# KegWasher_1_2_Schematic_EasyEDA.net
KiCad netlist of a schematic drawn in EasyEDA
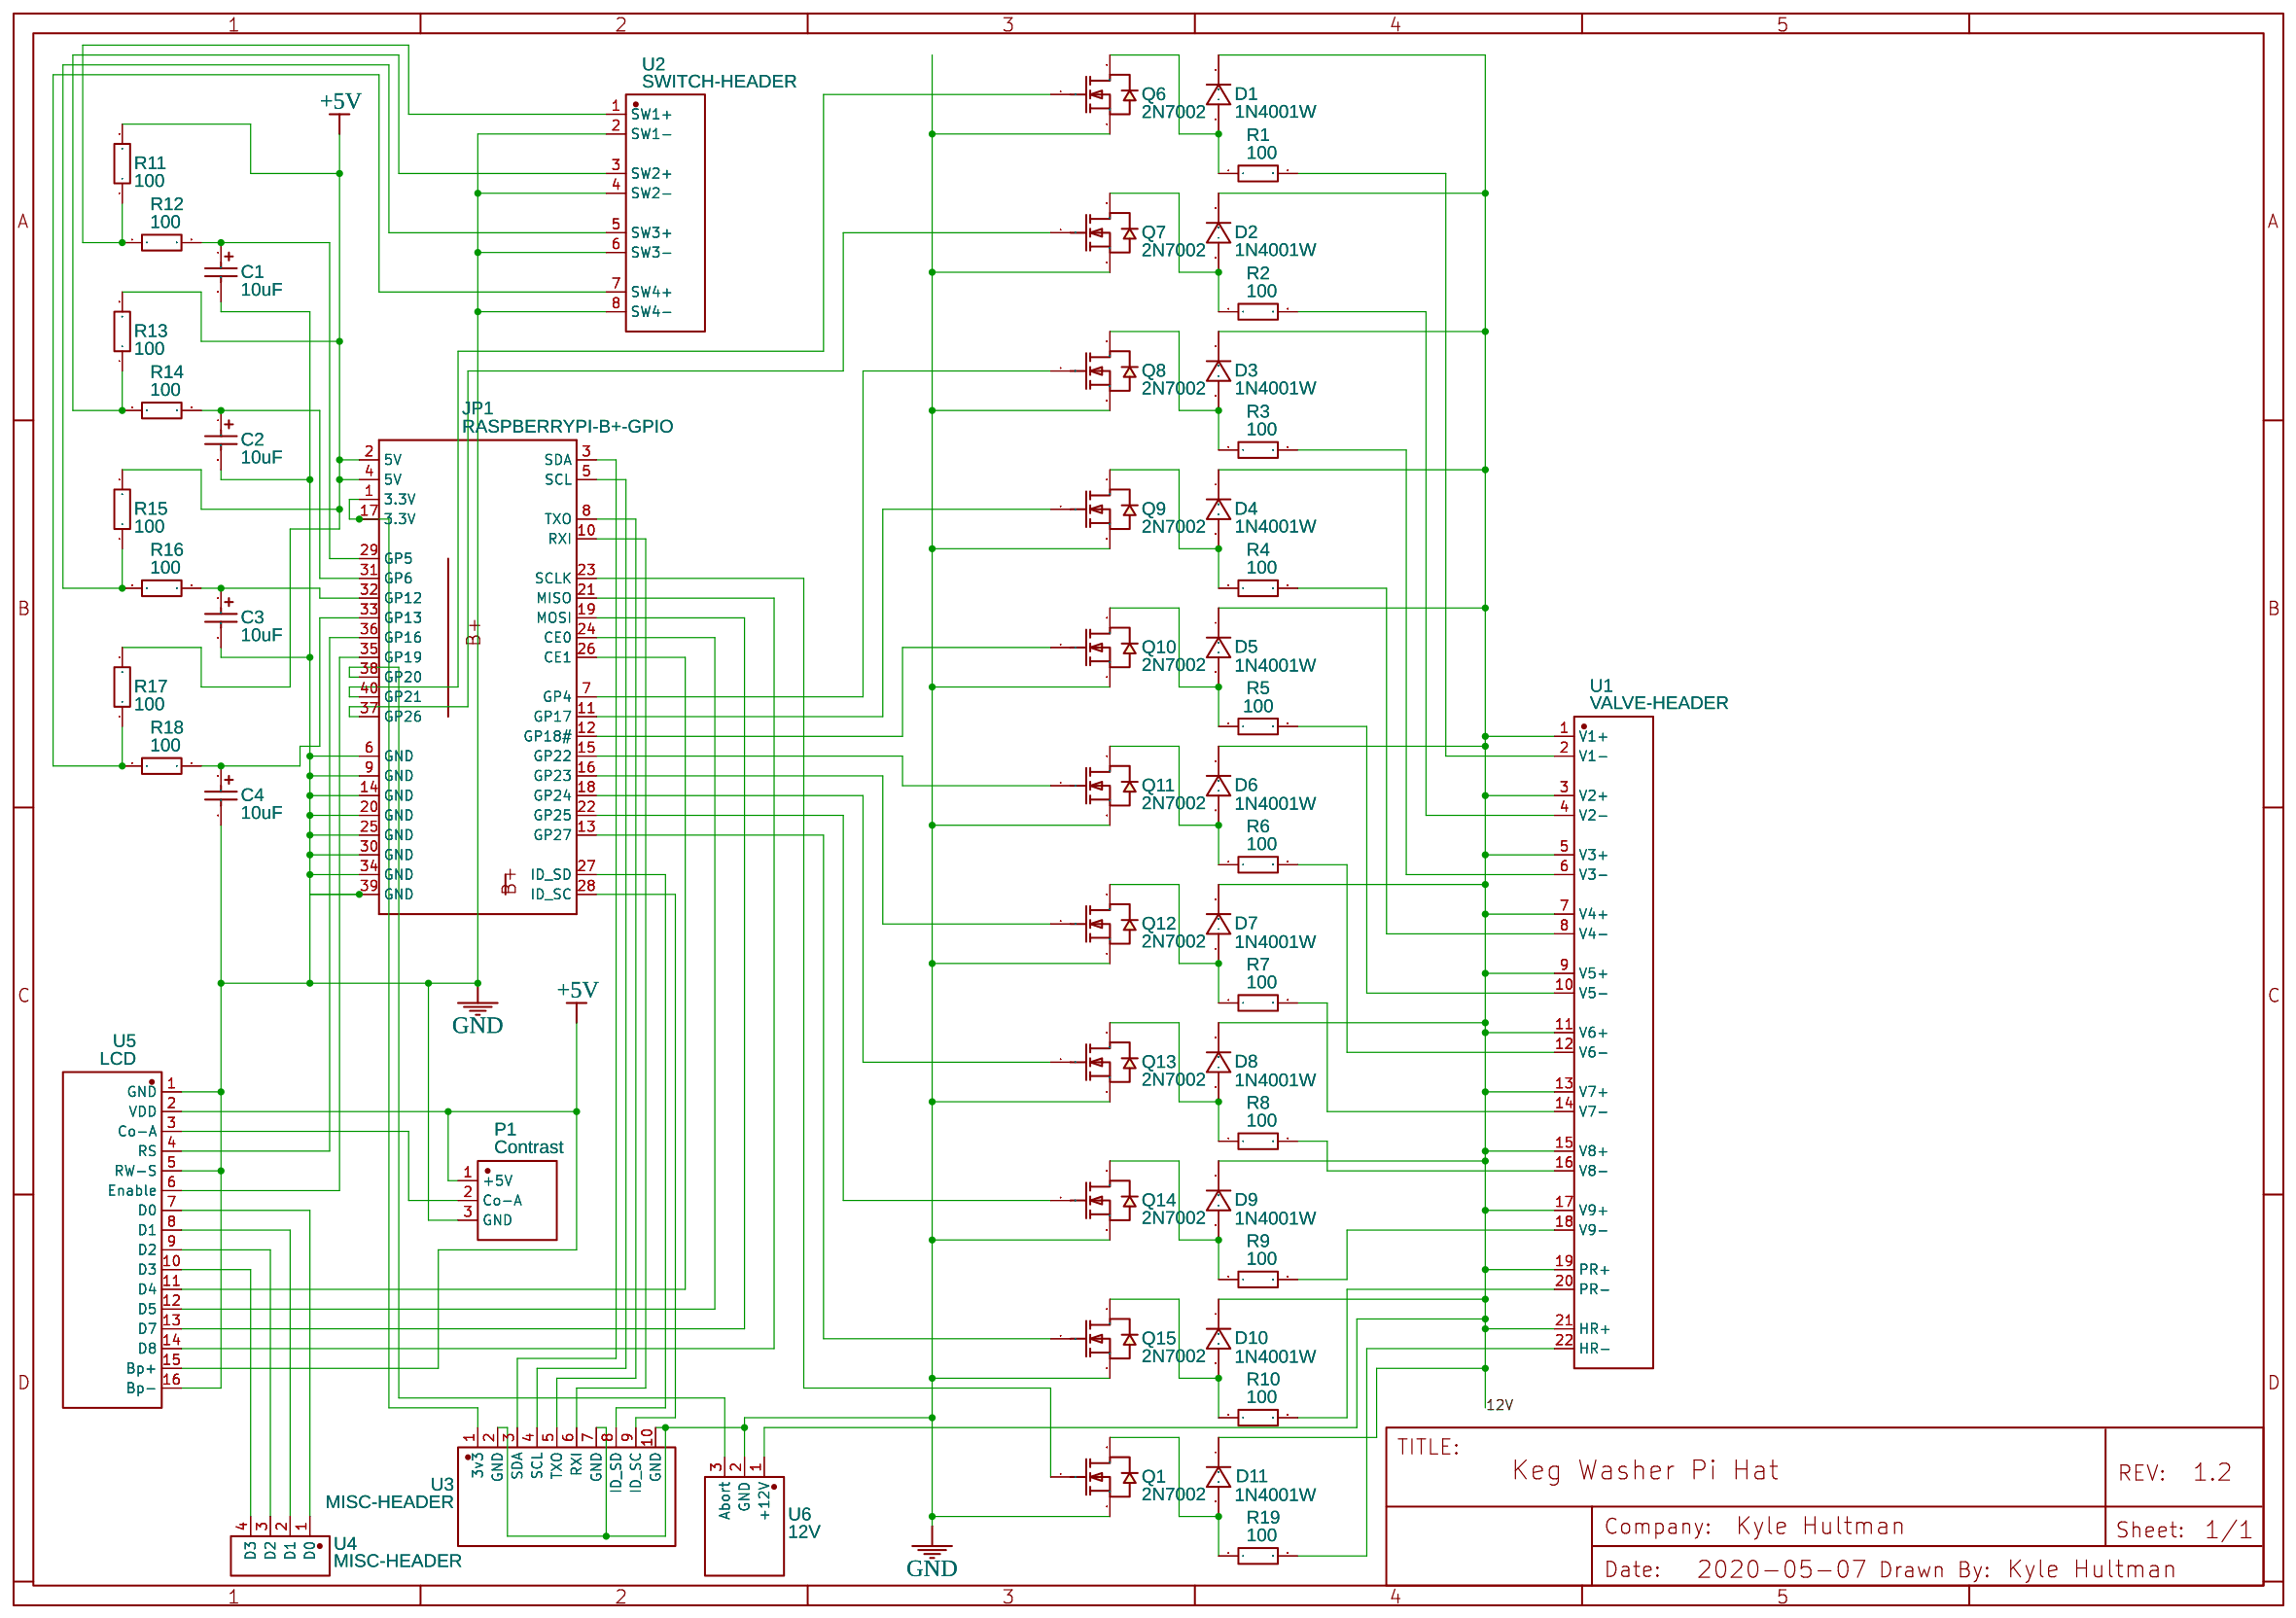
[diagram p0: schematic sheet]

(export (version "E")
  (design (tool "Eeschema 10.0.6"))
  (components
    (comp (ref "C1")
      (value "10uF")
      (fields
        (field (name "BOM_Manufacturer Part") "TAJA106K016RNJ")
        (field (name "BOM_Supplier Part") "C7171")
      )
      (libsource (lib "") (part "TAJA106K016RNJ"))
    )
    (comp (ref "C2")
      (value "10uF")
      (fields
        (field (name "BOM_Manufacturer Part") "TAJA106K016RNJ")
        (field (name "BOM_Supplier Part") "C7171")
      )
      (libsource (lib "") (part "TAJA106K016RNJ"))
    )
    (comp (ref "C3")
      (value "10uF")
      (fields
        (field (name "BOM_Manufacturer Part") "TAJA106K016RNJ")
        (field (name "BOM_Supplier Part") "C7171")
      )
      (libsource (lib "") (part "TAJA106K016RNJ"))
    )
    (comp (ref "C4")
      (value "10uF")
      (fields
        (field (name "BOM_Manufacturer Part") "TAJA106K016RNJ")
        (field (name "BOM_Supplier Part") "C7171")
      )
      (libsource (lib "") (part "TAJA106K016RNJ"))
    )
    (comp (ref "D1")
      (value "1N4001W")
      (fields (field (name "BOM_Supplier Part") "C162732"))
      (libsource (lib "") (part "1N4001W"))
    )
    (comp (ref "D2")
      (value "1N4001W")
      (fields (field (name "BOM_Supplier Part") "C162732"))
      (libsource (lib "") (part "1N4001W"))
    )
    (comp (ref "D3")
      (value "1N4001W")
      (fields (field (name "BOM_Supplier Part") "C162732"))
      (libsource (lib "") (part "1N4001W"))
    )
    (comp (ref "D4")
      (value "1N4001W")
      (fields (field (name "BOM_Supplier Part") "C162732"))
      (libsource (lib "") (part "1N4001W"))
    )
    (comp (ref "D5")
      (value "1N4001W")
      (fields (field (name "BOM_Supplier Part") "C162732"))
      (libsource (lib "") (part "1N4001W"))
    )
    (comp (ref "D6")
      (value "1N4001W")
      (fields (field (name "BOM_Supplier Part") "C162732"))
      (libsource (lib "") (part "1N4001W"))
    )
    (comp (ref "D7")
      (value "1N4001W")
      (fields (field (name "BOM_Supplier Part") "C162732"))
      (libsource (lib "") (part "1N4001W"))
    )
    (comp (ref "D8")
      (value "1N4001W")
      (fields (field (name "BOM_Supplier Part") "C162732"))
      (libsource (lib "") (part "1N4001W"))
    )
    (comp (ref "D9")
      (value "1N4001W")
      (fields (field (name "BOM_Supplier Part") "C162732"))
      (libsource (lib "") (part "1N4001W"))
    )
    (comp (ref "D10")
      (value "1N4001W")
      (fields (field (name "BOM_Supplier Part") "C162732"))
      (libsource (lib "") (part "1N4001W"))
    )
    (comp (ref "D11")
      (value "1N4001W")
      (fields (field (name "BOM_Supplier Part") "C162732"))
      (libsource (lib "") (part "1N4001W"))
    )
    (comp (ref "JP1") (value "RASPBERRYPI-B+-GPIO") (libsource (lib "") (part "RASPBERRYPI-B+-GPIO")))
    (comp (ref "P1") (value "Contrast") (libsource (lib "") (part "Contrast")))
    (comp (ref "Q1")
      (value "2N7002")
      (fields (field (name "BOM_Supplier Part") "C8545"))
      (libsource (lib "") (part "2N7002"))
    )
    (comp (ref "Q6")
      (value "2N7002")
      (fields (field (name "BOM_Supplier Part") "C8545"))
      (libsource (lib "") (part "2N7002"))
    )
    (comp (ref "Q7")
      (value "2N7002")
      (fields (field (name "BOM_Supplier Part") "C8545"))
      (libsource (lib "") (part "2N7002"))
    )
    (comp (ref "Q8")
      (value "2N7002")
      (fields (field (name "BOM_Supplier Part") "C8545"))
      (libsource (lib "") (part "2N7002"))
    )
    (comp (ref "Q9")
      (value "2N7002")
      (fields (field (name "BOM_Supplier Part") "C8545"))
      (libsource (lib "") (part "2N7002"))
    )
    (comp (ref "Q10")
      (value "2N7002")
      (fields (field (name "BOM_Supplier Part") "C8545"))
      (libsource (lib "") (part "2N7002"))
    )
    (comp (ref "Q11")
      (value "2N7002")
      (fields (field (name "BOM_Supplier Part") "C8545"))
      (libsource (lib "") (part "2N7002"))
    )
    (comp (ref "Q12")
      (value "2N7002")
      (fields (field (name "BOM_Supplier Part") "C8545"))
      (libsource (lib "") (part "2N7002"))
    )
    (comp (ref "Q13")
      (value "2N7002")
      (fields (field (name "BOM_Supplier Part") "C8545"))
      (libsource (lib "") (part "2N7002"))
    )
    (comp (ref "Q14")
      (value "2N7002")
      (fields (field (name "BOM_Supplier Part") "C8545"))
      (libsource (lib "") (part "2N7002"))
    )
    (comp (ref "Q15")
      (value "2N7002")
      (fields (field (name "BOM_Supplier Part") "C8545"))
      (libsource (lib "") (part "2N7002"))
    )
    (comp (ref "R1")
      (value "100")
      (fields
        (field (name "BOM_Manufacturer Part") "0805W8F1000T5E")
        (field (name "BOM_Supplier Part") "C17408")
      )
      (libsource (lib "") (part "0805W8F1000T5E"))
    )
    (comp (ref "R2")
      (value "100")
      (fields
        (field (name "BOM_Manufacturer Part") "0805W8F1000T5E")
        (field (name "BOM_Supplier Part") "C17408")
      )
      (libsource (lib "") (part "0805W8F1000T5E"))
    )
    (comp (ref "R3")
      (value "100")
      (fields
        (field (name "BOM_Manufacturer Part") "0805W8F1000T5E")
        (field (name "BOM_Supplier Part") "C17408")
      )
      (libsource (lib "") (part "0805W8F1000T5E"))
    )
    (comp (ref "R4")
      (value "100")
      (fields
        (field (name "BOM_Manufacturer Part") "0805W8F1000T5E")
        (field (name "BOM_Supplier Part") "C17408")
      )
      (libsource (lib "") (part "0805W8F1000T5E"))
    )
    (comp (ref "R5")
      (value "100")
      (fields
        (field (name "BOM_Manufacturer Part") "0805W8F1000T5E")
        (field (name "BOM_Supplier Part") "C17408")
      )
      (libsource (lib "") (part "0805W8F1000T5E"))
    )
    (comp (ref "R6")
      (value "100")
      (fields
        (field (name "BOM_Manufacturer Part") "0805W8F1000T5E")
        (field (name "BOM_Supplier Part") "C17408")
      )
      (libsource (lib "") (part "0805W8F1000T5E"))
    )
    (comp (ref "R7")
      (value "100")
      (fields
        (field (name "BOM_Manufacturer Part") "0805W8F1000T5E")
        (field (name "BOM_Supplier Part") "C17408")
      )
      (libsource (lib "") (part "0805W8F1000T5E"))
    )
    (comp (ref "R8")
      (value "100")
      (fields
        (field (name "BOM_Manufacturer Part") "0805W8F1000T5E")
        (field (name "BOM_Supplier Part") "C17408")
      )
      (libsource (lib "") (part "0805W8F1000T5E"))
    )
    (comp (ref "R9")
      (value "100")
      (fields
        (field (name "BOM_Manufacturer Part") "0805W8F1000T5E")
        (field (name "BOM_Supplier Part") "C17408")
      )
      (libsource (lib "") (part "0805W8F1000T5E"))
    )
    (comp (ref "R10")
      (value "100")
      (fields
        (field (name "BOM_Manufacturer Part") "0805W8F1000T5E")
        (field (name "BOM_Supplier Part") "C17408")
      )
      (libsource (lib "") (part "0805W8F1000T5E"))
    )
    (comp (ref "R11")
      (value "100")
      (fields
        (field (name "BOM_Manufacturer Part") "0805W8F1000T5E")
        (field (name "BOM_Supplier Part") "C17408")
      )
      (libsource (lib "") (part "0805W8F1000T5E_1"))
    )
    (comp (ref "R12")
      (value "100")
      (fields
        (field (name "BOM_Manufacturer Part") "0805W8F1000T5E")
        (field (name "BOM_Supplier Part") "C17408")
      )
      (libsource (lib "") (part "0805W8F1000T5E"))
    )
    (comp (ref "R13")
      (value "100")
      (fields
        (field (name "BOM_Manufacturer Part") "0805W8F1000T5E")
        (field (name "BOM_Supplier Part") "C17408")
      )
      (libsource (lib "") (part "0805W8F1000T5E_1"))
    )
    (comp (ref "R14")
      (value "100")
      (fields
        (field (name "BOM_Manufacturer Part") "0805W8F1000T5E")
        (field (name "BOM_Supplier Part") "C17408")
      )
      (libsource (lib "") (part "0805W8F1000T5E"))
    )
    (comp (ref "R15")
      (value "100")
      (fields
        (field (name "BOM_Manufacturer Part") "0805W8F1000T5E")
        (field (name "BOM_Supplier Part") "C17408")
      )
      (libsource (lib "") (part "0805W8F1000T5E_1"))
    )
    (comp (ref "R16")
      (value "100")
      (fields
        (field (name "BOM_Manufacturer Part") "0805W8F1000T5E")
        (field (name "BOM_Supplier Part") "C17408")
      )
      (libsource (lib "") (part "0805W8F1000T5E"))
    )
    (comp (ref "R17")
      (value "100")
      (fields
        (field (name "BOM_Manufacturer Part") "0805W8F1000T5E")
        (field (name "BOM_Supplier Part") "C17408")
      )
      (libsource (lib "") (part "0805W8F1000T5E_1"))
    )
    (comp (ref "R18")
      (value "100")
      (fields
        (field (name "BOM_Manufacturer Part") "0805W8F1000T5E")
        (field (name "BOM_Supplier Part") "C17408")
      )
      (libsource (lib "") (part "0805W8F1000T5E"))
    )
    (comp (ref "R19")
      (value "100")
      (fields
        (field (name "BOM_Manufacturer Part") "0805W8F1000T5E")
        (field (name "BOM_Supplier Part") "C17408")
      )
      (libsource (lib "") (part "0805W8F1000T5E"))
    )
    (comp (ref "U1") (value "VALVE-HEADER") (libsource (lib "") (part "VALVE-HEADER")))
    (comp (ref "U2") (value "SWITCH-HEADER") (libsource (lib "") (part "SWITCH-HEADER")))
    (comp (ref "U3") (value "MISC-HEADER") (libsource (lib "") (part "MISC-HEADER_1")))
    (comp (ref "U4") (value "MISC-HEADER") (libsource (lib "") (part "MISC-HEADER")))
    (comp (ref "U5") (value "LCD") (libsource (lib "") (part "LCD")))
    (comp (ref "U6") (value "12V") (libsource (lib "") (part "12V")))
  )
  (nets
    (net (code "1") (name "+5V") (class "Default")
      (node (ref "JP1") (pin "2") (pinfunction "5V_2") (pintype "passive"))
      (node (ref "JP1") (pin "4") (pinfunction "5V_4") (pintype "passive"))
      (node (ref "P1") (pin "1") (pinfunction "+5V_1") (pintype "unspecified"))
      (node (ref "R11") (pin "2") (pinfunction "2_2") (pintype "input"))
      (node (ref "R13") (pin "2") (pinfunction "2_2") (pintype "input"))
      (node (ref "R15") (pin "2") (pinfunction "2_2") (pintype "input"))
      (node (ref "R17") (pin "2") (pinfunction "2_2") (pintype "input"))
      (node (ref "U5") (pin "15") (pinfunction "Bp+_15") (pintype "unspecified"))
      (node (ref "U5") (pin "2") (pinfunction "VDD_2") (pintype "unspecified"))
    )
    (net (code "2") (name "/12V") (class "Default")
      (node (ref "D1") (pin "1") (pinfunction "C_1") (pintype "unspecified"))
      (node (ref "D10") (pin "1") (pinfunction "C_1") (pintype "unspecified"))
      (node (ref "D11") (pin "1") (pinfunction "C_1") (pintype "unspecified"))
      (node (ref "D2") (pin "1") (pinfunction "C_1") (pintype "unspecified"))
      (node (ref "D3") (pin "1") (pinfunction "C_1") (pintype "unspecified"))
      (node (ref "D4") (pin "1") (pinfunction "C_1") (pintype "unspecified"))
      (node (ref "D5") (pin "1") (pinfunction "C_1") (pintype "unspecified"))
      (node (ref "D6") (pin "1") (pinfunction "C_1") (pintype "unspecified"))
      (node (ref "D7") (pin "1") (pinfunction "C_1") (pintype "unspecified"))
      (node (ref "D8") (pin "1") (pinfunction "C_1") (pintype "unspecified"))
      (node (ref "D9") (pin "1") (pinfunction "C_1") (pintype "unspecified"))
      (node (ref "U1") (pin "1") (pinfunction "V1+_1") (pintype "unspecified"))
      (node (ref "U1") (pin "11") (pinfunction "V6+_11") (pintype "unspecified"))
      (node (ref "U1") (pin "13") (pinfunction "V7+_13") (pintype "unspecified"))
      (node (ref "U1") (pin "15") (pinfunction "V8+_15") (pintype "unspecified"))
      (node (ref "U1") (pin "17") (pinfunction "V9+_17") (pintype "unspecified"))
      (node (ref "U1") (pin "19") (pinfunction "PR+_19") (pintype "unspecified"))
      (node (ref "U1") (pin "21") (pinfunction "HR+_21") (pintype "unspecified"))
      (node (ref "U1") (pin "3") (pinfunction "V2+_3") (pintype "unspecified"))
      (node (ref "U1") (pin "5") (pinfunction "V3+_5") (pintype "unspecified"))
      (node (ref "U1") (pin "7") (pinfunction "V4+_7") (pintype "unspecified"))
      (node (ref "U1") (pin "9") (pinfunction "V5+_9") (pintype "unspecified"))
      (node (ref "U6") (pin "1") (pinfunction "+12V_1") (pintype "unspecified"))
    )
    (net (code "3") (name "GND") (class "Default")
      (node (ref "C1") (pin "2") (pinfunction "2_2") (pintype "input"))
      (node (ref "C2") (pin "2") (pinfunction "2_2") (pintype "input"))
      (node (ref "C3") (pin "2") (pinfunction "2_2") (pintype "input"))
      (node (ref "C4") (pin "2") (pinfunction "2_2") (pintype "input"))
      (node (ref "JP1") (pin "14") (pinfunction "GND_14") (pintype "passive"))
      (node (ref "JP1") (pin "20") (pinfunction "GND_20") (pintype "passive"))
      (node (ref "JP1") (pin "25") (pinfunction "GND_25") (pintype "passive"))
      (node (ref "JP1") (pin "30") (pinfunction "GND_30") (pintype "passive"))
      (node (ref "JP1") (pin "34") (pinfunction "GND_34") (pintype "passive"))
      (node (ref "JP1") (pin "39") (pinfunction "GND_39") (pintype "passive"))
      (node (ref "JP1") (pin "6") (pinfunction "GND_6") (pintype "passive"))
      (node (ref "JP1") (pin "9") (pinfunction "GND_9") (pintype "passive"))
      (node (ref "P1") (pin "3") (pinfunction "GND_3") (pintype "unspecified"))
      (node (ref "Q1") (pin "2") (pinfunction "S_2") (pintype "unspecified"))
      (node (ref "Q10") (pin "2") (pinfunction "S_2") (pintype "unspecified"))
      (node (ref "Q11") (pin "2") (pinfunction "S_2") (pintype "unspecified"))
      (node (ref "Q12") (pin "2") (pinfunction "S_2") (pintype "unspecified"))
      (node (ref "Q13") (pin "2") (pinfunction "S_2") (pintype "unspecified"))
      (node (ref "Q14") (pin "2") (pinfunction "S_2") (pintype "unspecified"))
      (node (ref "Q15") (pin "2") (pinfunction "S_2") (pintype "unspecified"))
      (node (ref "Q6") (pin "2") (pinfunction "S_2") (pintype "unspecified"))
      (node (ref "Q7") (pin "2") (pinfunction "S_2") (pintype "unspecified"))
      (node (ref "Q8") (pin "2") (pinfunction "S_2") (pintype "unspecified"))
      (node (ref "Q9") (pin "2") (pinfunction "S_2") (pintype "unspecified"))
      (node (ref "U2") (pin "2") (pinfunction "SW1-_2") (pintype "unspecified"))
      (node (ref "U2") (pin "4") (pinfunction "SW2-_4") (pintype "unspecified"))
      (node (ref "U2") (pin "6") (pinfunction "SW3-_6") (pintype "unspecified"))
      (node (ref "U2") (pin "8") (pinfunction "SW4-_8") (pintype "unspecified"))
      (node (ref "U3") (pin "10") (pinfunction "GND_10") (pintype "unspecified"))
      (node (ref "U3") (pin "2") (pinfunction "GND_2") (pintype "unspecified"))
      (node (ref "U3") (pin "7") (pinfunction "GND_7") (pintype "unspecified"))
      (node (ref "U5") (pin "1") (pinfunction "GND_1") (pintype "unspecified"))
      (node (ref "U5") (pin "16") (pinfunction "Bp-_16") (pintype "unspecified"))
      (node (ref "U5") (pin "5") (pinfunction "RW-S_5") (pintype "unspecified"))
      (node (ref "U6") (pin "2") (pinfunction "GND_2") (pintype "unspecified"))
    )
    (net (code "4") (name "Net-(D1-A)") (class "Default")
      (node (ref "D1") (pin "2") (pinfunction "A_2") (pintype "unspecified"))
      (node (ref "Q6") (pin "3") (pinfunction "D_3") (pintype "unspecified"))
      (node (ref "R1") (pin "1") (pinfunction "1_1") (pintype "input"))
    )
    (net (code "5") (name "Net-(D2-A)") (class "Default")
      (node (ref "D2") (pin "2") (pinfunction "A_2") (pintype "unspecified"))
      (node (ref "Q7") (pin "3") (pinfunction "D_3") (pintype "unspecified"))
      (node (ref "R2") (pin "1") (pinfunction "1_1") (pintype "input"))
    )
    (net (code "6") (name "Net-(D3-A)") (class "Default")
      (node (ref "D3") (pin "2") (pinfunction "A_2") (pintype "unspecified"))
      (node (ref "Q8") (pin "3") (pinfunction "D_3") (pintype "unspecified"))
      (node (ref "R3") (pin "1") (pinfunction "1_1") (pintype "input"))
    )
    (net (code "7") (name "Net-(D4-A)") (class "Default")
      (node (ref "D4") (pin "2") (pinfunction "A_2") (pintype "unspecified"))
      (node (ref "Q9") (pin "3") (pinfunction "D_3") (pintype "unspecified"))
      (node (ref "R4") (pin "1") (pinfunction "1_1") (pintype "input"))
    )
    (net (code "8") (name "Net-(D5-A)") (class "Default")
      (node (ref "D5") (pin "2") (pinfunction "A_2") (pintype "unspecified"))
      (node (ref "Q10") (pin "3") (pinfunction "D_3") (pintype "unspecified"))
      (node (ref "R5") (pin "1") (pinfunction "1_1") (pintype "input"))
    )
    (net (code "9") (name "Net-(D6-A)") (class "Default")
      (node (ref "D6") (pin "2") (pinfunction "A_2") (pintype "unspecified"))
      (node (ref "Q11") (pin "3") (pinfunction "D_3") (pintype "unspecified"))
      (node (ref "R6") (pin "1") (pinfunction "1_1") (pintype "input"))
    )
    (net (code "10") (name "Net-(D7-A)") (class "Default")
      (node (ref "D7") (pin "2") (pinfunction "A_2") (pintype "unspecified"))
      (node (ref "Q12") (pin "3") (pinfunction "D_3") (pintype "unspecified"))
      (node (ref "R7") (pin "1") (pinfunction "1_1") (pintype "input"))
    )
    (net (code "11") (name "Net-(D8-A)") (class "Default")
      (node (ref "D8") (pin "2") (pinfunction "A_2") (pintype "unspecified"))
      (node (ref "Q13") (pin "3") (pinfunction "D_3") (pintype "unspecified"))
      (node (ref "R8") (pin "1") (pinfunction "1_1") (pintype "input"))
    )
    (net (code "12") (name "Net-(D9-A)") (class "Default")
      (node (ref "D9") (pin "2") (pinfunction "A_2") (pintype "unspecified"))
      (node (ref "Q14") (pin "3") (pinfunction "D_3") (pintype "unspecified"))
      (node (ref "R9") (pin "1") (pinfunction "1_1") (pintype "input"))
    )
    (net (code "13") (name "Net-(D10-A)") (class "Default")
      (node (ref "D10") (pin "2") (pinfunction "A_2") (pintype "unspecified"))
      (node (ref "Q15") (pin "3") (pinfunction "D_3") (pintype "unspecified"))
      (node (ref "R10") (pin "1") (pinfunction "1_1") (pintype "input"))
    )
    (net (code "14") (name "Net-(D11-A)") (class "Default")
      (node (ref "D11") (pin "2") (pinfunction "A_2") (pintype "unspecified"))
      (node (ref "Q1") (pin "3") (pinfunction "D_3") (pintype "unspecified"))
      (node (ref "R19") (pin "1") (pinfunction "1_1") (pintype "input"))
    )
    (net (code "15") (name "Net-(JP1-CE0)") (class "Default")
      (node (ref "JP1") (pin "24") (pinfunction "CE0_24") (pintype "output"))
      (node (ref "U5") (pin "12") (pinfunction "D5_12") (pintype "unspecified"))
    )
    (net (code "16") (name "Net-(JP1-CE1)") (class "Default")
      (node (ref "JP1") (pin "26") (pinfunction "CE1_26") (pintype "output"))
      (node (ref "U5") (pin "11") (pinfunction "D4_11") (pintype "unspecified"))
    )
    (net (code "17") (name "Net-(JP1-GP4)") (class "Default")
      (node (ref "JP1") (pin "7") (pinfunction "GP4_7") (pintype "unspecified"))
      (node (ref "Q8") (pin "1") (pinfunction "G_1") (pintype "unspecified"))
    )
    (net (code "18") (name "Net-(JP1-GP5)") (class "Default")
      (node (ref "C1") (pin "1") (pinfunction "1_1") (pintype "input"))
      (node (ref "JP1") (pin "29") (pinfunction "GP5_29") (pintype "unspecified"))
      (node (ref "R12") (pin "2") (pinfunction "2_2") (pintype "input"))
    )
    (net (code "19") (name "Net-(JP1-GP6)") (class "Default")
      (node (ref "C2") (pin "1") (pinfunction "1_1") (pintype "input"))
      (node (ref "JP1") (pin "31") (pinfunction "GP6_31") (pintype "unspecified"))
      (node (ref "R14") (pin "2") (pinfunction "2_2") (pintype "input"))
    )
    (net (code "20") (name "Net-(JP1-GP12)") (class "Default")
      (node (ref "C3") (pin "1") (pinfunction "1_1") (pintype "input"))
      (node (ref "JP1") (pin "32") (pinfunction "GP12_32") (pintype "unspecified"))
      (node (ref "R16") (pin "2") (pinfunction "2_2") (pintype "input"))
    )
    (net (code "21") (name "Net-(JP1-GP13)") (class "Default")
      (node (ref "C4") (pin "1") (pinfunction "1_1") (pintype "input"))
      (node (ref "JP1") (pin "33") (pinfunction "GP13_33") (pintype "unspecified"))
      (node (ref "R18") (pin "2") (pinfunction "2_2") (pintype "input"))
    )
    (net (code "22") (name "Net-(JP1-GP16)") (class "Default")
      (node (ref "JP1") (pin "36") (pinfunction "GP16_36") (pintype "unspecified"))
      (node (ref "U5") (pin "4") (pinfunction "RS_4") (pintype "unspecified"))
    )
    (net (code "23") (name "Net-(JP1-GP17)") (class "Default")
      (node (ref "JP1") (pin "11") (pinfunction "GP17_11") (pintype "unspecified"))
      (node (ref "Q9") (pin "1") (pinfunction "G_1") (pintype "unspecified"))
    )
    (net (code "24") (name "Net-(JP1-GP18#)") (class "Default")
      (node (ref "JP1") (pin "12") (pinfunction "GP18#_12") (pintype "unspecified"))
      (node (ref "Q10") (pin "1") (pinfunction "G_1") (pintype "unspecified"))
    )
    (net (code "25") (name "Net-(JP1-GP19)") (class "Default")
      (node (ref "JP1") (pin "35") (pinfunction "GP19_35") (pintype "unspecified"))
      (node (ref "U5") (pin "6") (pinfunction "Enable_6") (pintype "unspecified"))
    )
    (net (code "26") (name "Net-(JP1-GP20)") (class "Default")
      (node (ref "JP1") (pin "38") (pinfunction "GP20_38") (pintype "unspecified"))
      (node (ref "U6") (pin "3") (pinfunction "Abort_3") (pintype "unspecified"))
    )
    (net (code "27") (name "Net-(JP1-GP21)") (class "Default")
      (node (ref "JP1") (pin "40") (pinfunction "GP21_40") (pintype "unspecified"))
      (node (ref "Q6") (pin "1") (pinfunction "G_1") (pintype "unspecified"))
    )
    (net (code "28") (name "Net-(JP1-GP22)") (class "Default")
      (node (ref "JP1") (pin "15") (pinfunction "GP22_15") (pintype "unspecified"))
      (node (ref "Q11") (pin "1") (pinfunction "G_1") (pintype "unspecified"))
    )
    (net (code "29") (name "Net-(JP1-GP23)") (class "Default")
      (node (ref "JP1") (pin "16") (pinfunction "GP23_16") (pintype "unspecified"))
      (node (ref "Q12") (pin "1") (pinfunction "G_1") (pintype "unspecified"))
    )
    (net (code "30") (name "Net-(JP1-GP24)") (class "Default")
      (node (ref "JP1") (pin "18") (pinfunction "GP24_18") (pintype "unspecified"))
      (node (ref "Q13") (pin "1") (pinfunction "G_1") (pintype "unspecified"))
    )
    (net (code "31") (name "Net-(JP1-GP25)") (class "Default")
      (node (ref "JP1") (pin "22") (pinfunction "GP25_22") (pintype "unspecified"))
      (node (ref "Q14") (pin "1") (pinfunction "G_1") (pintype "unspecified"))
    )
    (net (code "32") (name "Net-(JP1-GP26)") (class "Default")
      (node (ref "JP1") (pin "37") (pinfunction "GP26_37") (pintype "unspecified"))
      (node (ref "Q7") (pin "1") (pinfunction "G_1") (pintype "unspecified"))
    )
    (net (code "33") (name "Net-(JP1-GP27)") (class "Default")
      (node (ref "JP1") (pin "13") (pinfunction "GP27_13") (pintype "unspecified"))
      (node (ref "Q15") (pin "1") (pinfunction "G_1") (pintype "unspecified"))
    )
    (net (code "34") (name "Net-(JP1-ID_SC)") (class "Default")
      (node (ref "JP1") (pin "28") (pinfunction "ID_SC_28") (pintype "unspecified"))
      (node (ref "U3") (pin "9") (pinfunction "ID_SC_9") (pintype "unspecified"))
    )
    (net (code "35") (name "Net-(JP1-ID_SD)") (class "Default")
      (node (ref "JP1") (pin "27") (pinfunction "ID_SD_27") (pintype "unspecified"))
      (node (ref "U3") (pin "8") (pinfunction "ID_SD_8") (pintype "unspecified"))
    )
    (net (code "36") (name "Net-(JP1-MISO)") (class "Default")
      (node (ref "JP1") (pin "21") (pinfunction "MISO_21") (pintype "input"))
      (node (ref "U5") (pin "14") (pinfunction "D8_14") (pintype "unspecified"))
    )
    (net (code "37") (name "Net-(JP1-MOSI)") (class "Default")
      (node (ref "JP1") (pin "19") (pinfunction "MOSI_19") (pintype "output"))
      (node (ref "U5") (pin "13") (pinfunction "D7_13") (pintype "unspecified"))
    )
    (net (code "38") (name "Net-(JP1-RXI)") (class "Default")
      (node (ref "JP1") (pin "10") (pinfunction "RXI_10") (pintype "input"))
      (node (ref "U3") (pin "6") (pinfunction "RXI_6") (pintype "unspecified"))
    )
    (net (code "39") (name "Net-(JP1-SCL)") (class "Default")
      (node (ref "JP1") (pin "5") (pinfunction "SCL_5") (pintype "unspecified"))
      (node (ref "U3") (pin "4") (pinfunction "SCL_4") (pintype "unspecified"))
    )
    (net (code "40") (name "Net-(JP1-SCLK)") (class "Default")
      (node (ref "JP1") (pin "23") (pinfunction "SCLK_23") (pintype "output"))
      (node (ref "Q1") (pin "1") (pinfunction "G_1") (pintype "unspecified"))
    )
    (net (code "41") (name "Net-(JP1-SDA)") (class "Default")
      (node (ref "JP1") (pin "3") (pinfunction "SDA_3") (pintype "unspecified"))
      (node (ref "U3") (pin "3") (pinfunction "SDA_3") (pintype "unspecified"))
    )
    (net (code "42") (name "Net-(JP1-TXO)") (class "Default")
      (node (ref "JP1") (pin "8") (pinfunction "TXO_8") (pintype "output"))
      (node (ref "U3") (pin "5") (pinfunction "TXO_5") (pintype "unspecified"))
    )
    (net (code "43") (name "Net-(P1-Co-A)") (class "Default")
      (node (ref "P1") (pin "2") (pinfunction "Co-A_2") (pintype "unspecified"))
      (node (ref "U5") (pin "3") (pinfunction "Co-A_3") (pintype "unspecified"))
    )
    (net (code "44") (name "Net-(U1-HR-)") (class "Default")
      (node (ref "R19") (pin "2") (pinfunction "2_2") (pintype "input"))
      (node (ref "U1") (pin "22") (pinfunction "HR-_22") (pintype "unspecified"))
    )
    (net (code "45") (name "Net-(U1-PR-)") (class "Default")
      (node (ref "R10") (pin "2") (pinfunction "2_2") (pintype "input"))
      (node (ref "U1") (pin "20") (pinfunction "PR-_20") (pintype "unspecified"))
    )
    (net (code "46") (name "Net-(U1-V1-)") (class "Default")
      (node (ref "R1") (pin "2") (pinfunction "2_2") (pintype "input"))
      (node (ref "U1") (pin "2") (pinfunction "V1-_2") (pintype "unspecified"))
    )
    (net (code "47") (name "Net-(U1-V2-)") (class "Default")
      (node (ref "R2") (pin "2") (pinfunction "2_2") (pintype "input"))
      (node (ref "U1") (pin "4") (pinfunction "V2-_4") (pintype "unspecified"))
    )
    (net (code "48") (name "Net-(U1-V3-)") (class "Default")
      (node (ref "R3") (pin "2") (pinfunction "2_2") (pintype "input"))
      (node (ref "U1") (pin "6") (pinfunction "V3-_6") (pintype "unspecified"))
    )
    (net (code "49") (name "Net-(U1-V4-)") (class "Default")
      (node (ref "R4") (pin "2") (pinfunction "2_2") (pintype "input"))
      (node (ref "U1") (pin "8") (pinfunction "V4-_8") (pintype "unspecified"))
    )
    (net (code "50") (name "Net-(U1-V5-)") (class "Default")
      (node (ref "R5") (pin "2") (pinfunction "2_2") (pintype "input"))
      (node (ref "U1") (pin "10") (pinfunction "V5-_10") (pintype "unspecified"))
    )
    (net (code "51") (name "Net-(U1-V6-)") (class "Default")
      (node (ref "R6") (pin "2") (pinfunction "2_2") (pintype "input"))
      (node (ref "U1") (pin "12") (pinfunction "V6-_12") (pintype "unspecified"))
    )
    (net (code "52") (name "Net-(U1-V7-)") (class "Default")
      (node (ref "R7") (pin "2") (pinfunction "2_2") (pintype "input"))
      (node (ref "U1") (pin "14") (pinfunction "V7-_14") (pintype "unspecified"))
    )
    (net (code "53") (name "Net-(U1-V8-)") (class "Default")
      (node (ref "R8") (pin "2") (pinfunction "2_2") (pintype "input"))
      (node (ref "U1") (pin "16") (pinfunction "V8-_16") (pintype "unspecified"))
    )
    (net (code "54") (name "Net-(U1-V9-)") (class "Default")
      (node (ref "R9") (pin "2") (pinfunction "2_2") (pintype "input"))
      (node (ref "U1") (pin "18") (pinfunction "V9-_18") (pintype "unspecified"))
    )
    (net (code "55") (name "Net-(U2-SW1+)") (class "Default")
      (node (ref "R11") (pin "1") (pinfunction "1_1") (pintype "input"))
      (node (ref "R12") (pin "1") (pinfunction "1_1") (pintype "input"))
      (node (ref "U2") (pin "1") (pinfunction "SW1+_1") (pintype "unspecified"))
    )
    (net (code "56") (name "Net-(U2-SW2+)") (class "Default")
      (node (ref "R13") (pin "1") (pinfunction "1_1") (pintype "input"))
      (node (ref "R14") (pin "1") (pinfunction "1_1") (pintype "input"))
      (node (ref "U2") (pin "3") (pinfunction "SW2+_3") (pintype "unspecified"))
    )
    (net (code "57") (name "Net-(U2-SW3+)") (class "Default")
      (node (ref "R15") (pin "1") (pinfunction "1_1") (pintype "input"))
      (node (ref "R16") (pin "1") (pinfunction "1_1") (pintype "input"))
      (node (ref "U2") (pin "5") (pinfunction "SW3+_5") (pintype "unspecified"))
    )
    (net (code "58") (name "Net-(U2-SW4+)") (class "Default")
      (node (ref "R17") (pin "1") (pinfunction "1_1") (pintype "input"))
      (node (ref "R18") (pin "1") (pinfunction "1_1") (pintype "input"))
      (node (ref "U2") (pin "7") (pinfunction "SW4+_7") (pintype "unspecified"))
    )
    (net (code "59") (name "Net-(U3-3v3)") (class "Default")
      (node (ref "JP1") (pin "1") (pinfunction "3.3V_1") (pintype "passive"))
      (node (ref "JP1") (pin "17") (pinfunction "3.3V_17") (pintype "passive"))
      (node (ref "U3") (pin "1") (pinfunction "3v3_1") (pintype "unspecified"))
    )
    (net (code "60") (name "Net-(U4-D0)") (class "Default")
      (node (ref "U4") (pin "1") (pinfunction "D0_1") (pintype "unspecified"))
      (node (ref "U5") (pin "7") (pinfunction "D0_7") (pintype "unspecified"))
    )
    (net (code "61") (name "Net-(U4-D1)") (class "Default")
      (node (ref "U4") (pin "2") (pinfunction "D1_2") (pintype "unspecified"))
      (node (ref "U5") (pin "8") (pinfunction "D1_8") (pintype "unspecified"))
    )
    (net (code "62") (name "Net-(U4-D2)") (class "Default")
      (node (ref "U4") (pin "3") (pinfunction "D2_3") (pintype "unspecified"))
      (node (ref "U5") (pin "9") (pinfunction "D2_9") (pintype "unspecified"))
    )
    (net (code "63") (name "Net-(U4-D3)") (class "Default")
      (node (ref "U4") (pin "4") (pinfunction "D3_4") (pintype "unspecified"))
      (node (ref "U5") (pin "10") (pinfunction "D3_10") (pintype "unspecified"))
    )
  )
)
